# retroBreadboard_v1i1.net
KiCad netlist of a schematic drawn in Altium Designer
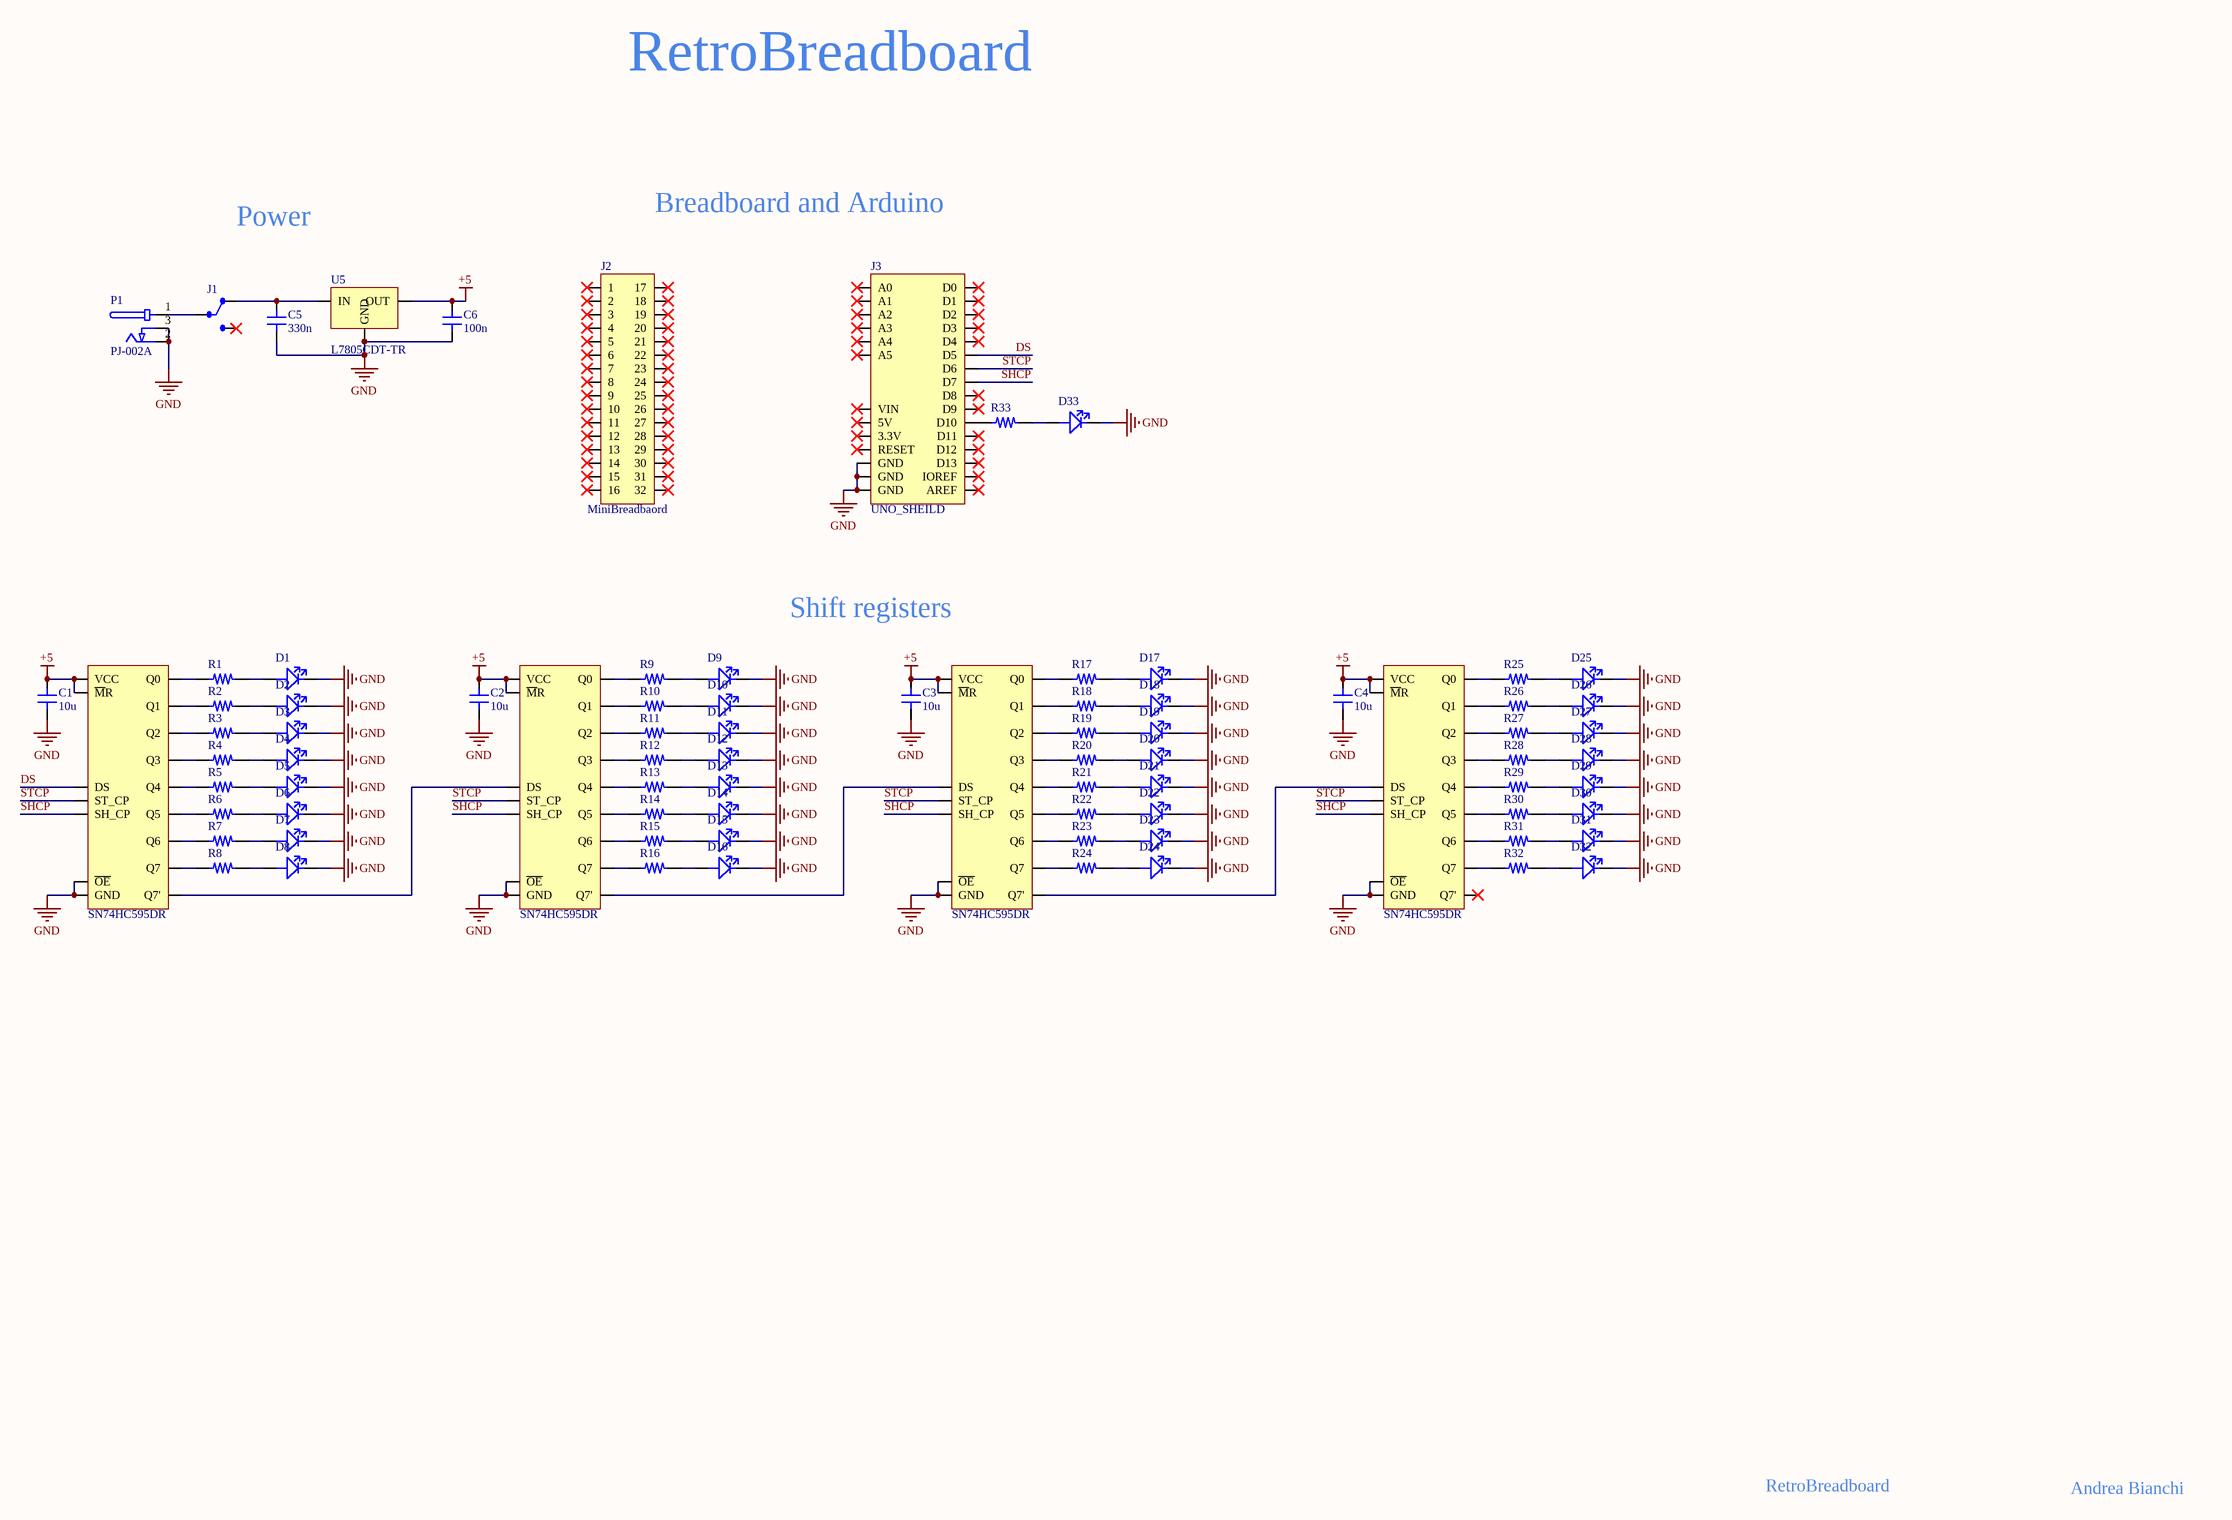
[diagram p0: retroBreadboard_v1i1.SchDoc]

(export (version "E")
  (design (tool "Eeschema 10.0.6"))
  (components
    (comp (ref "C1")
      (value "10u")
      (footprint "C0805")
      (fields
        (field (name "MANUFACTURER") "Samsung")
        (field (name "MANUFACTURER PART NUMBER") "CL21A106KQFNNNG")
        (field (name "TOLERANCE") "10%")
      )
      (libsource (lib "retroBreadboard_v1i1") (part "C0805_10u"))
    )
    (comp (ref "C2")
      (value "10u")
      (footprint "C0805")
      (fields
        (field (name "MANUFACTURER") "Samsung")
        (field (name "MANUFACTURER PART NUMBER") "CL21A106KQFNNNG")
        (field (name "TOLERANCE") "10%")
      )
      (libsource (lib "retroBreadboard_v1i1") (part "C0805_10u"))
    )
    (comp (ref "C3")
      (value "10u")
      (footprint "C0805")
      (fields
        (field (name "MANUFACTURER") "Samsung")
        (field (name "MANUFACTURER PART NUMBER") "CL21A106KQFNNNG")
        (field (name "TOLERANCE") "10%")
      )
      (libsource (lib "retroBreadboard_v1i1") (part "C0805_10u"))
    )
    (comp (ref "C4")
      (value "10u")
      (footprint "C0805")
      (fields
        (field (name "MANUFACTURER") "Samsung")
        (field (name "MANUFACTURER PART NUMBER") "CL21A106KQFNNNG")
        (field (name "TOLERANCE") "10%")
      )
      (libsource (lib "retroBreadboard_v1i1") (part "C0805_10u"))
    )
    (comp (ref "C5")
      (value "330n")
      (footprint "C0805")
      (fields
        (field (name "MANUFACTURER") "Samsung")
        (field (name "MANUFACTURER PART NUMBER") "CL21B334KAFNNNG")
        (field (name "TOLERANCE") "10%")
      )
      (libsource (lib "retroBreadboard_v1i1") (part "C0805_330n"))
    )
    (comp (ref "C6")
      (value "100n")
      (footprint "C0805")
      (fields
        (field (name "MANUFACTURER") "Samsung")
        (field (name "MANUFACTURER PART NUMBER") "CL21F104ZBCNNNC")
        (field (name "TOLERANCE") "80%")
      )
      (libsource (lib "retroBreadboard_v1i1") (part "C0805_100n"))
    )
    (comp (ref "D1")
      (value "VLMB1500-GS08")
      (footprint "VLMB1500-GS08")
      (description "Standard LEDs - SMD 0402 BLUE Non-Diff")
      (fields (field (name "MANUFACTURER") "Vishay"))
      (libsource (lib "retroBreadboard_v1i1") (part "VLMB1500-GS08"))
    )
    (comp (ref "D2")
      (value "VLMB1500-GS08")
      (footprint "VLMB1500-GS08")
      (description "Standard LEDs - SMD 0402 BLUE Non-Diff")
      (fields (field (name "MANUFACTURER") "Vishay"))
      (libsource (lib "retroBreadboard_v1i1") (part "VLMB1500-GS08"))
    )
    (comp (ref "D3")
      (value "VLMB1500-GS08")
      (footprint "VLMB1500-GS08")
      (description "Standard LEDs - SMD 0402 BLUE Non-Diff")
      (fields (field (name "MANUFACTURER") "Vishay"))
      (libsource (lib "retroBreadboard_v1i1") (part "VLMB1500-GS08"))
    )
    (comp (ref "D4")
      (value "VLMB1500-GS08")
      (footprint "VLMB1500-GS08")
      (description "Standard LEDs - SMD 0402 BLUE Non-Diff")
      (fields (field (name "MANUFACTURER") "Vishay"))
      (libsource (lib "retroBreadboard_v1i1") (part "VLMB1500-GS08"))
    )
    (comp (ref "D5")
      (value "VLMB1500-GS08")
      (footprint "VLMB1500-GS08")
      (description "Standard LEDs - SMD 0402 BLUE Non-Diff")
      (fields (field (name "MANUFACTURER") "Vishay"))
      (libsource (lib "retroBreadboard_v1i1") (part "VLMB1500-GS08"))
    )
    (comp (ref "D6")
      (value "VLMB1500-GS08")
      (footprint "VLMB1500-GS08")
      (description "Standard LEDs - SMD 0402 BLUE Non-Diff")
      (fields (field (name "MANUFACTURER") "Vishay"))
      (libsource (lib "retroBreadboard_v1i1") (part "VLMB1500-GS08"))
    )
    (comp (ref "D7")
      (value "VLMB1500-GS08")
      (footprint "VLMB1500-GS08")
      (description "Standard LEDs - SMD 0402 BLUE Non-Diff")
      (fields (field (name "MANUFACTURER") "Vishay"))
      (libsource (lib "retroBreadboard_v1i1") (part "VLMB1500-GS08"))
    )
    (comp (ref "D8")
      (value "VLMB1500-GS08")
      (footprint "VLMB1500-GS08")
      (description "Standard LEDs - SMD 0402 BLUE Non-Diff")
      (fields (field (name "MANUFACTURER") "Vishay"))
      (libsource (lib "retroBreadboard_v1i1") (part "VLMB1500-GS08"))
    )
    (comp (ref "D9")
      (value "VLMB1500-GS08")
      (footprint "VLMB1500-GS08")
      (description "Standard LEDs - SMD 0402 BLUE Non-Diff")
      (fields (field (name "MANUFACTURER") "Vishay"))
      (libsource (lib "retroBreadboard_v1i1") (part "VLMB1500-GS08"))
    )
    (comp (ref "D10")
      (value "VLMB1500-GS08")
      (footprint "VLMB1500-GS08")
      (description "Standard LEDs - SMD 0402 BLUE Non-Diff")
      (fields (field (name "MANUFACTURER") "Vishay"))
      (libsource (lib "retroBreadboard_v1i1") (part "VLMB1500-GS08"))
    )
    (comp (ref "D11")
      (value "VLMB1500-GS08")
      (footprint "VLMB1500-GS08")
      (description "Standard LEDs - SMD 0402 BLUE Non-Diff")
      (fields (field (name "MANUFACTURER") "Vishay"))
      (libsource (lib "retroBreadboard_v1i1") (part "VLMB1500-GS08"))
    )
    (comp (ref "D12")
      (value "VLMB1500-GS08")
      (footprint "VLMB1500-GS08")
      (description "Standard LEDs - SMD 0402 BLUE Non-Diff")
      (fields (field (name "MANUFACTURER") "Vishay"))
      (libsource (lib "retroBreadboard_v1i1") (part "VLMB1500-GS08"))
    )
    (comp (ref "D13")
      (value "VLMB1500-GS08")
      (footprint "VLMB1500-GS08")
      (description "Standard LEDs - SMD 0402 BLUE Non-Diff")
      (fields (field (name "MANUFACTURER") "Vishay"))
      (libsource (lib "retroBreadboard_v1i1") (part "VLMB1500-GS08"))
    )
    (comp (ref "D14")
      (value "VLMB1500-GS08")
      (footprint "VLMB1500-GS08")
      (description "Standard LEDs - SMD 0402 BLUE Non-Diff")
      (fields (field (name "MANUFACTURER") "Vishay"))
      (libsource (lib "retroBreadboard_v1i1") (part "VLMB1500-GS08"))
    )
    (comp (ref "D15")
      (value "VLMB1500-GS08")
      (footprint "VLMB1500-GS08")
      (description "Standard LEDs - SMD 0402 BLUE Non-Diff")
      (fields (field (name "MANUFACTURER") "Vishay"))
      (libsource (lib "retroBreadboard_v1i1") (part "VLMB1500-GS08"))
    )
    (comp (ref "D16")
      (value "VLMB1500-GS08")
      (footprint "VLMB1500-GS08")
      (description "Standard LEDs - SMD 0402 BLUE Non-Diff")
      (fields (field (name "MANUFACTURER") "Vishay"))
      (libsource (lib "retroBreadboard_v1i1") (part "VLMB1500-GS08"))
    )
    (comp (ref "D17")
      (value "VLMB1500-GS08")
      (footprint "VLMB1500-GS08")
      (description "Standard LEDs - SMD 0402 BLUE Non-Diff")
      (fields (field (name "MANUFACTURER") "Vishay"))
      (libsource (lib "retroBreadboard_v1i1") (part "VLMB1500-GS08"))
    )
    (comp (ref "D18")
      (value "VLMB1500-GS08")
      (footprint "VLMB1500-GS08")
      (description "Standard LEDs - SMD 0402 BLUE Non-Diff")
      (fields (field (name "MANUFACTURER") "Vishay"))
      (libsource (lib "retroBreadboard_v1i1") (part "VLMB1500-GS08"))
    )
    (comp (ref "D19")
      (value "VLMB1500-GS08")
      (footprint "VLMB1500-GS08")
      (description "Standard LEDs - SMD 0402 BLUE Non-Diff")
      (fields (field (name "MANUFACTURER") "Vishay"))
      (libsource (lib "retroBreadboard_v1i1") (part "VLMB1500-GS08"))
    )
    (comp (ref "D20")
      (value "VLMB1500-GS08")
      (footprint "VLMB1500-GS08")
      (description "Standard LEDs - SMD 0402 BLUE Non-Diff")
      (fields (field (name "MANUFACTURER") "Vishay"))
      (libsource (lib "retroBreadboard_v1i1") (part "VLMB1500-GS08"))
    )
    (comp (ref "D21")
      (value "VLMB1500-GS08")
      (footprint "VLMB1500-GS08")
      (description "Standard LEDs - SMD 0402 BLUE Non-Diff")
      (fields (field (name "MANUFACTURER") "Vishay"))
      (libsource (lib "retroBreadboard_v1i1") (part "VLMB1500-GS08"))
    )
    (comp (ref "D22")
      (value "VLMB1500-GS08")
      (footprint "VLMB1500-GS08")
      (description "Standard LEDs - SMD 0402 BLUE Non-Diff")
      (fields (field (name "MANUFACTURER") "Vishay"))
      (libsource (lib "retroBreadboard_v1i1") (part "VLMB1500-GS08"))
    )
    (comp (ref "D23")
      (value "VLMB1500-GS08")
      (footprint "VLMB1500-GS08")
      (description "Standard LEDs - SMD 0402 BLUE Non-Diff")
      (fields (field (name "MANUFACTURER") "Vishay"))
      (libsource (lib "retroBreadboard_v1i1") (part "VLMB1500-GS08"))
    )
    (comp (ref "D24")
      (value "VLMB1500-GS08")
      (footprint "VLMB1500-GS08")
      (description "Standard LEDs - SMD 0402 BLUE Non-Diff")
      (fields (field (name "MANUFACTURER") "Vishay"))
      (libsource (lib "retroBreadboard_v1i1") (part "VLMB1500-GS08"))
    )
    (comp (ref "D25")
      (value "VLMB1500-GS08")
      (footprint "VLMB1500-GS08")
      (description "Standard LEDs - SMD 0402 BLUE Non-Diff")
      (fields (field (name "MANUFACTURER") "Vishay"))
      (libsource (lib "retroBreadboard_v1i1") (part "VLMB1500-GS08"))
    )
    (comp (ref "D26")
      (value "VLMB1500-GS08")
      (footprint "VLMB1500-GS08")
      (description "Standard LEDs - SMD 0402 BLUE Non-Diff")
      (fields (field (name "MANUFACTURER") "Vishay"))
      (libsource (lib "retroBreadboard_v1i1") (part "VLMB1500-GS08"))
    )
    (comp (ref "D27")
      (value "VLMB1500-GS08")
      (footprint "VLMB1500-GS08")
      (description "Standard LEDs - SMD 0402 BLUE Non-Diff")
      (fields (field (name "MANUFACTURER") "Vishay"))
      (libsource (lib "retroBreadboard_v1i1") (part "VLMB1500-GS08"))
    )
    (comp (ref "D28")
      (value "VLMB1500-GS08")
      (footprint "VLMB1500-GS08")
      (description "Standard LEDs - SMD 0402 BLUE Non-Diff")
      (fields (field (name "MANUFACTURER") "Vishay"))
      (libsource (lib "retroBreadboard_v1i1") (part "VLMB1500-GS08"))
    )
    (comp (ref "D29")
      (value "VLMB1500-GS08")
      (footprint "VLMB1500-GS08")
      (description "Standard LEDs - SMD 0402 BLUE Non-Diff")
      (fields (field (name "MANUFACTURER") "Vishay"))
      (libsource (lib "retroBreadboard_v1i1") (part "VLMB1500-GS08"))
    )
    (comp (ref "D30")
      (value "VLMB1500-GS08")
      (footprint "VLMB1500-GS08")
      (description "Standard LEDs - SMD 0402 BLUE Non-Diff")
      (fields (field (name "MANUFACTURER") "Vishay"))
      (libsource (lib "retroBreadboard_v1i1") (part "VLMB1500-GS08"))
    )
    (comp (ref "D31")
      (value "VLMB1500-GS08")
      (footprint "VLMB1500-GS08")
      (description "Standard LEDs - SMD 0402 BLUE Non-Diff")
      (fields (field (name "MANUFACTURER") "Vishay"))
      (libsource (lib "retroBreadboard_v1i1") (part "VLMB1500-GS08"))
    )
    (comp (ref "D32")
      (value "VLMB1500-GS08")
      (footprint "VLMB1500-GS08")
      (description "Standard LEDs - SMD 0402 BLUE Non-Diff")
      (fields (field (name "MANUFACTURER") "Vishay"))
      (libsource (lib "retroBreadboard_v1i1") (part "VLMB1500-GS08"))
    )
    (comp (ref "D33")
      (value "VLMB1500-GS08")
      (footprint "VLMB1500-GS08")
      (description "Standard LEDs - SMD 0402 BLUE Non-Diff")
      (fields (field (name "MANUFACTURER") "Vishay"))
      (libsource (lib "retroBreadboard_v1i1") (part "VLMB1500-GS08"))
    )
    (comp (ref "J1")
      (value "500SSP1S1M6QEA")
      (footprint "SLIDE SPDT")
      (description "SWITCH SLIDE SPDT 5A 120V")
      (fields (field (name "MANUFACTURER") "E-Switch"))
      (libsource (lib "retroBreadboard_v1i1") (part "SLIDE SPDT"))
    )
    (comp (ref "J2")
      (value "MiniBreadbaord")
      (footprint "MINI_BREADBOARD HOLE")
      (description "Mini Breadboard")
      (fields
        (field (name "MANUFACTURER") "TE Connectivity AMP")
        (field (name "MANUFACTURER PART NUMBER") "1738132-1")
      )
      (libsource (lib "retroBreadboard_v1i1") (part "MINI_BREADBOARD"))
    )
    (comp (ref "J3")
      (value "UNO_SHEILD")
      (footprint "ARDUINO_UNO_SHIELD")
      (libsource (lib "retroBreadboard_v1i1") (part "ARDUINO_UNO_SHIELD"))
    )
    (comp (ref "P1")
      (value "PJ-002A")
      (footprint "PJ-002A")
      (description "PJ-002 Series 2 x 6.5 mm 16 V Right Angle Through Hole Power Jack")
      (fields (field (name "MANUFACTURER") "CUI"))
      (libsource (lib "retroBreadboard_v1i1") (part "PJ-002A"))
    )
    (comp (ref "R1")
      (value "RC0402FR-07200RL")
      (footprint "RES0402")
      (description "RES SMD 200 OHM 1% 1/16W 0402")
      (fields (field (name "MANUFACTURER") "Yageo") (field (name "TOLERANCE") "1%"))
      (libsource (lib "retroBreadboard_v1i1") (part "R0402_200"))
    )
    (comp (ref "R2")
      (value "RC0402FR-07200RL")
      (footprint "RES0402")
      (description "RES SMD 200 OHM 1% 1/16W 0402")
      (fields (field (name "MANUFACTURER") "Yageo") (field (name "TOLERANCE") "1%"))
      (libsource (lib "retroBreadboard_v1i1") (part "R0402_200"))
    )
    (comp (ref "R3")
      (value "RC0402FR-07200RL")
      (footprint "RES0402")
      (description "RES SMD 200 OHM 1% 1/16W 0402")
      (fields (field (name "MANUFACTURER") "Yageo") (field (name "TOLERANCE") "1%"))
      (libsource (lib "retroBreadboard_v1i1") (part "R0402_200"))
    )
    (comp (ref "R4")
      (value "RC0402FR-07200RL")
      (footprint "RES0402")
      (description "RES SMD 200 OHM 1% 1/16W 0402")
      (fields (field (name "MANUFACTURER") "Yageo") (field (name "TOLERANCE") "1%"))
      (libsource (lib "retroBreadboard_v1i1") (part "R0402_200"))
    )
    (comp (ref "R5")
      (value "RC0402FR-07200RL")
      (footprint "RES0402")
      (description "RES SMD 200 OHM 1% 1/16W 0402")
      (fields (field (name "MANUFACTURER") "Yageo") (field (name "TOLERANCE") "1%"))
      (libsource (lib "retroBreadboard_v1i1") (part "R0402_200"))
    )
    (comp (ref "R6")
      (value "RC0402FR-07200RL")
      (footprint "RES0402")
      (description "RES SMD 200 OHM 1% 1/16W 0402")
      (fields (field (name "MANUFACTURER") "Yageo") (field (name "TOLERANCE") "1%"))
      (libsource (lib "retroBreadboard_v1i1") (part "R0402_200"))
    )
    (comp (ref "R7")
      (value "RC0402FR-07200RL")
      (footprint "RES0402")
      (description "RES SMD 200 OHM 1% 1/16W 0402")
      (fields (field (name "MANUFACTURER") "Yageo") (field (name "TOLERANCE") "1%"))
      (libsource (lib "retroBreadboard_v1i1") (part "R0402_200"))
    )
    (comp (ref "R8")
      (value "RC0402FR-07200RL")
      (footprint "RES0402")
      (description "RES SMD 200 OHM 1% 1/16W 0402")
      (fields (field (name "MANUFACTURER") "Yageo") (field (name "TOLERANCE") "1%"))
      (libsource (lib "retroBreadboard_v1i1") (part "R0402_200"))
    )
    (comp (ref "R9")
      (value "RC0402FR-07200RL")
      (footprint "RES0402")
      (description "RES SMD 200 OHM 1% 1/16W 0402")
      (fields (field (name "MANUFACTURER") "Yageo") (field (name "TOLERANCE") "1%"))
      (libsource (lib "retroBreadboard_v1i1") (part "R0402_200"))
    )
    (comp (ref "R10")
      (value "RC0402FR-07200RL")
      (footprint "RES0402")
      (description "RES SMD 200 OHM 1% 1/16W 0402")
      (fields (field (name "MANUFACTURER") "Yageo") (field (name "TOLERANCE") "1%"))
      (libsource (lib "retroBreadboard_v1i1") (part "R0402_200"))
    )
    (comp (ref "R11")
      (value "RC0402FR-07200RL")
      (footprint "RES0402")
      (description "RES SMD 200 OHM 1% 1/16W 0402")
      (fields (field (name "MANUFACTURER") "Yageo") (field (name "TOLERANCE") "1%"))
      (libsource (lib "retroBreadboard_v1i1") (part "R0402_200"))
    )
    (comp (ref "R12")
      (value "RC0402FR-07200RL")
      (footprint "RES0402")
      (description "RES SMD 200 OHM 1% 1/16W 0402")
      (fields (field (name "MANUFACTURER") "Yageo") (field (name "TOLERANCE") "1%"))
      (libsource (lib "retroBreadboard_v1i1") (part "R0402_200"))
    )
    (comp (ref "R13")
      (value "RC0402FR-07200RL")
      (footprint "RES0402")
      (description "RES SMD 200 OHM 1% 1/16W 0402")
      (fields (field (name "MANUFACTURER") "Yageo") (field (name "TOLERANCE") "1%"))
      (libsource (lib "retroBreadboard_v1i1") (part "R0402_200"))
    )
    (comp (ref "R14")
      (value "RC0402FR-07200RL")
      (footprint "RES0402")
      (description "RES SMD 200 OHM 1% 1/16W 0402")
      (fields (field (name "MANUFACTURER") "Yageo") (field (name "TOLERANCE") "1%"))
      (libsource (lib "retroBreadboard_v1i1") (part "R0402_200"))
    )
    (comp (ref "R15")
      (value "RC0402FR-07200RL")
      (footprint "RES0402")
      (description "RES SMD 200 OHM 1% 1/16W 0402")
      (fields (field (name "MANUFACTURER") "Yageo") (field (name "TOLERANCE") "1%"))
      (libsource (lib "retroBreadboard_v1i1") (part "R0402_200"))
    )
    (comp (ref "R16")
      (value "RC0402FR-07200RL")
      (footprint "RES0402")
      (description "RES SMD 200 OHM 1% 1/16W 0402")
      (fields (field (name "MANUFACTURER") "Yageo") (field (name "TOLERANCE") "1%"))
      (libsource (lib "retroBreadboard_v1i1") (part "R0402_200"))
    )
    (comp (ref "R17")
      (value "RC0402FR-07200RL")
      (footprint "RES0402")
      (description "RES SMD 200 OHM 1% 1/16W 0402")
      (fields (field (name "MANUFACTURER") "Yageo") (field (name "TOLERANCE") "1%"))
      (libsource (lib "retroBreadboard_v1i1") (part "R0402_200"))
    )
    (comp (ref "R18")
      (value "RC0402FR-07200RL")
      (footprint "RES0402")
      (description "RES SMD 200 OHM 1% 1/16W 0402")
      (fields (field (name "MANUFACTURER") "Yageo") (field (name "TOLERANCE") "1%"))
      (libsource (lib "retroBreadboard_v1i1") (part "R0402_200"))
    )
    (comp (ref "R19")
      (value "RC0402FR-07200RL")
      (footprint "RES0402")
      (description "RES SMD 200 OHM 1% 1/16W 0402")
      (fields (field (name "MANUFACTURER") "Yageo") (field (name "TOLERANCE") "1%"))
      (libsource (lib "retroBreadboard_v1i1") (part "R0402_200"))
    )
    (comp (ref "R20")
      (value "RC0402FR-07200RL")
      (footprint "RES0402")
      (description "RES SMD 200 OHM 1% 1/16W 0402")
      (fields (field (name "MANUFACTURER") "Yageo") (field (name "TOLERANCE") "1%"))
      (libsource (lib "retroBreadboard_v1i1") (part "R0402_200"))
    )
    (comp (ref "R21")
      (value "RC0402FR-07200RL")
      (footprint "RES0402")
      (description "RES SMD 200 OHM 1% 1/16W 0402")
      (fields (field (name "MANUFACTURER") "Yageo") (field (name "TOLERANCE") "1%"))
      (libsource (lib "retroBreadboard_v1i1") (part "R0402_200"))
    )
    (comp (ref "R22")
      (value "RC0402FR-07200RL")
      (footprint "RES0402")
      (description "RES SMD 200 OHM 1% 1/16W 0402")
      (fields (field (name "MANUFACTURER") "Yageo") (field (name "TOLERANCE") "1%"))
      (libsource (lib "retroBreadboard_v1i1") (part "R0402_200"))
    )
    (comp (ref "R23")
      (value "RC0402FR-07200RL")
      (footprint "RES0402")
      (description "RES SMD 200 OHM 1% 1/16W 0402")
      (fields (field (name "MANUFACTURER") "Yageo") (field (name "TOLERANCE") "1%"))
      (libsource (lib "retroBreadboard_v1i1") (part "R0402_200"))
    )
    (comp (ref "R24")
      (value "RC0402FR-07200RL")
      (footprint "RES0402")
      (description "RES SMD 200 OHM 1% 1/16W 0402")
      (fields (field (name "MANUFACTURER") "Yageo") (field (name "TOLERANCE") "1%"))
      (libsource (lib "retroBreadboard_v1i1") (part "R0402_200"))
    )
    (comp (ref "R25")
      (value "RC0402FR-07200RL")
      (footprint "RES0402")
      (description "RES SMD 200 OHM 1% 1/16W 0402")
      (fields (field (name "MANUFACTURER") "Yageo") (field (name "TOLERANCE") "1%"))
      (libsource (lib "retroBreadboard_v1i1") (part "R0402_200"))
    )
    (comp (ref "R26")
      (value "RC0402FR-07200RL")
      (footprint "RES0402")
      (description "RES SMD 200 OHM 1% 1/16W 0402")
      (fields (field (name "MANUFACTURER") "Yageo") (field (name "TOLERANCE") "1%"))
      (libsource (lib "retroBreadboard_v1i1") (part "R0402_200"))
    )
    (comp (ref "R27")
      (value "RC0402FR-07200RL")
      (footprint "RES0402")
      (description "RES SMD 200 OHM 1% 1/16W 0402")
      (fields (field (name "MANUFACTURER") "Yageo") (field (name "TOLERANCE") "1%"))
      (libsource (lib "retroBreadboard_v1i1") (part "R0402_200"))
    )
    (comp (ref "R28")
      (value "RC0402FR-07200RL")
      (footprint "RES0402")
      (description "RES SMD 200 OHM 1% 1/16W 0402")
      (fields (field (name "MANUFACTURER") "Yageo") (field (name "TOLERANCE") "1%"))
      (libsource (lib "retroBreadboard_v1i1") (part "R0402_200"))
    )
    (comp (ref "R29")
      (value "RC0402FR-07200RL")
      (footprint "RES0402")
      (description "RES SMD 200 OHM 1% 1/16W 0402")
      (fields (field (name "MANUFACTURER") "Yageo") (field (name "TOLERANCE") "1%"))
      (libsource (lib "retroBreadboard_v1i1") (part "R0402_200"))
    )
    (comp (ref "R30")
      (value "RC0402FR-07200RL")
      (footprint "RES0402")
      (description "RES SMD 200 OHM 1% 1/16W 0402")
      (fields (field (name "MANUFACTURER") "Yageo") (field (name "TOLERANCE") "1%"))
      (libsource (lib "retroBreadboard_v1i1") (part "R0402_200"))
    )
    (comp (ref "R31")
      (value "RC0402FR-07200RL")
      (footprint "RES0402")
      (description "RES SMD 200 OHM 1% 1/16W 0402")
      (fields (field (name "MANUFACTURER") "Yageo") (field (name "TOLERANCE") "1%"))
      (libsource (lib "retroBreadboard_v1i1") (part "R0402_200"))
    )
    (comp (ref "R32")
      (value "RC0402FR-07200RL")
      (footprint "RES0402")
      (description "RES SMD 200 OHM 1% 1/16W 0402")
      (fields (field (name "MANUFACTURER") "Yageo") (field (name "TOLERANCE") "1%"))
      (libsource (lib "retroBreadboard_v1i1") (part "R0402_200"))
    )
    (comp (ref "R33")
      (value "RC0402FR-07200RL")
      (footprint "RES0402")
      (description "RES SMD 200 OHM 1% 1/16W 0402")
      (fields (field (name "MANUFACTURER") "Yageo") (field (name "TOLERANCE") "1%"))
      (libsource (lib "retroBreadboard_v1i1") (part "R0402_200"))
    )
    (comp (ref "U1")
      (value "SN74HC595DR")
      (footprint "SOIC16")
      (description "IC, SM, LOGIC, 74HC, REGISTER")
      (fields (field (name "MANUFACTURER") "Texas Instruments"))
      (libsource (lib "retroBreadboard_v1i1") (part "74HC595"))
    )
    (comp (ref "U2")
      (value "SN74HC595DR")
      (footprint "SOIC16")
      (description "IC, SM, LOGIC, 74HC, REGISTER")
      (fields (field (name "MANUFACTURER") "Texas Instruments"))
      (libsource (lib "retroBreadboard_v1i1") (part "74HC595"))
    )
    (comp (ref "U3")
      (value "SN74HC595DR")
      (footprint "SOIC16")
      (description "IC, SM, LOGIC, 74HC, REGISTER")
      (fields (field (name "MANUFACTURER") "Texas Instruments"))
      (libsource (lib "retroBreadboard_v1i1") (part "74HC595"))
    )
    (comp (ref "U4")
      (value "SN74HC595DR")
      (footprint "SOIC16")
      (description "IC, SM, LOGIC, 74HC, REGISTER")
      (fields (field (name "MANUFACTURER") "Texas Instruments"))
      (libsource (lib "retroBreadboard_v1i1") (part "74HC595"))
    )
    (comp (ref "U5")
      (value "L7805CDT-TR")
      (footprint "DPAK")
      (description "IC REG LDO 5V 1.5A DPAK")
      (fields (field (name "MANUFACTURER") "STMicroelectronics"))
      (libsource (lib "retroBreadboard_v1i1") (part "L7805CDT-TR"))
    )
  )
  (nets
    (net (code "1") (name "+5") (class "Default")
      (node (ref "C1") (pin "2") (pinfunction "2_2") (pintype "passive"))
      (node (ref "C2") (pin "2") (pinfunction "2_2") (pintype "passive"))
      (node (ref "C3") (pin "2") (pinfunction "2_2") (pintype "passive"))
      (node (ref "C4") (pin "2") (pinfunction "2_2") (pintype "passive"))
      (node (ref "C6") (pin "2") (pinfunction "2_2") (pintype "passive"))
      (node (ref "U1") (pin "10") (pinfunction "~{M}R_10") (pintype "passive"))
      (node (ref "U1") (pin "16") (pinfunction "VCC_16") (pintype "passive"))
      (node (ref "U2") (pin "10") (pinfunction "~{M}R_10") (pintype "passive"))
      (node (ref "U2") (pin "16") (pinfunction "VCC_16") (pintype "passive"))
      (node (ref "U3") (pin "10") (pinfunction "~{M}R_10") (pintype "passive"))
      (node (ref "U3") (pin "16") (pinfunction "VCC_16") (pintype "passive"))
      (node (ref "U4") (pin "10") (pinfunction "~{M}R_10") (pintype "passive"))
      (node (ref "U4") (pin "16") (pinfunction "VCC_16") (pintype "passive"))
      (node (ref "U5") (pin "3") (pinfunction "OUT_3") (pintype "passive"))
    )
    (net (code "2") (name "/DS") (class "Default")
      (node (ref "J3") (pin "6") (pinfunction "D5_6") (pintype "passive"))
      (node (ref "U1") (pin "14") (pinfunction "DS_14") (pintype "passive"))
    )
    (net (code "3") (name "/SHCP") (class "Default")
      (node (ref "J3") (pin "8") (pinfunction "D7_8") (pintype "passive"))
      (node (ref "U1") (pin "11") (pinfunction "SH_CP_11") (pintype "passive"))
      (node (ref "U2") (pin "11") (pinfunction "SH_CP_11") (pintype "passive"))
      (node (ref "U3") (pin "11") (pinfunction "SH_CP_11") (pintype "passive"))
      (node (ref "U4") (pin "11") (pinfunction "SH_CP_11") (pintype "passive"))
    )
    (net (code "4") (name "/STCP") (class "Default")
      (node (ref "J3") (pin "7") (pinfunction "D6_7") (pintype "passive"))
      (node (ref "U1") (pin "12") (pinfunction "ST_CP_12") (pintype "passive"))
      (node (ref "U2") (pin "12") (pinfunction "ST_CP_12") (pintype "passive"))
      (node (ref "U3") (pin "12") (pinfunction "ST_CP_12") (pintype "passive"))
      (node (ref "U4") (pin "12") (pinfunction "ST_CP_12") (pintype "passive"))
    )
    (net (code "5") (name "GND") (class "Default")
      (node (ref "C1") (pin "1") (pinfunction "1_1") (pintype "passive"))
      (node (ref "C2") (pin "1") (pinfunction "1_1") (pintype "passive"))
      (node (ref "C3") (pin "1") (pinfunction "1_1") (pintype "passive"))
      (node (ref "C4") (pin "1") (pinfunction "1_1") (pintype "passive"))
      (node (ref "C5") (pin "1") (pinfunction "1_1") (pintype "passive"))
      (node (ref "C6") (pin "1") (pinfunction "1_1") (pintype "passive"))
      (node (ref "D1") (pin "2") (pinfunction "K_2") (pintype "passive"))
      (node (ref "D10") (pin "2") (pinfunction "K_2") (pintype "passive"))
      (node (ref "D11") (pin "2") (pinfunction "K_2") (pintype "passive"))
      (node (ref "D12") (pin "2") (pinfunction "K_2") (pintype "passive"))
      (node (ref "D13") (pin "2") (pinfunction "K_2") (pintype "passive"))
      (node (ref "D14") (pin "2") (pinfunction "K_2") (pintype "passive"))
      (node (ref "D15") (pin "2") (pinfunction "K_2") (pintype "passive"))
      (node (ref "D16") (pin "2") (pinfunction "K_2") (pintype "passive"))
      (node (ref "D17") (pin "2") (pinfunction "K_2") (pintype "passive"))
      (node (ref "D18") (pin "2") (pinfunction "K_2") (pintype "passive"))
      (node (ref "D19") (pin "2") (pinfunction "K_2") (pintype "passive"))
      (node (ref "D2") (pin "2") (pinfunction "K_2") (pintype "passive"))
      (node (ref "D20") (pin "2") (pinfunction "K_2") (pintype "passive"))
      (node (ref "D21") (pin "2") (pinfunction "K_2") (pintype "passive"))
      (node (ref "D22") (pin "2") (pinfunction "K_2") (pintype "passive"))
      (node (ref "D23") (pin "2") (pinfunction "K_2") (pintype "passive"))
      (node (ref "D24") (pin "2") (pinfunction "K_2") (pintype "passive"))
      (node (ref "D25") (pin "2") (pinfunction "K_2") (pintype "passive"))
      (node (ref "D26") (pin "2") (pinfunction "K_2") (pintype "passive"))
      (node (ref "D27") (pin "2") (pinfunction "K_2") (pintype "passive"))
      (node (ref "D28") (pin "2") (pinfunction "K_2") (pintype "passive"))
      (node (ref "D29") (pin "2") (pinfunction "K_2") (pintype "passive"))
      (node (ref "D3") (pin "2") (pinfunction "K_2") (pintype "passive"))
      (node (ref "D30") (pin "2") (pinfunction "K_2") (pintype "passive"))
      (node (ref "D31") (pin "2") (pinfunction "K_2") (pintype "passive"))
      (node (ref "D32") (pin "2") (pinfunction "K_2") (pintype "passive"))
      (node (ref "D33") (pin "2") (pinfunction "K_2") (pintype "passive"))
      (node (ref "D4") (pin "2") (pinfunction "K_2") (pintype "passive"))
      (node (ref "D5") (pin "2") (pinfunction "K_2") (pintype "passive"))
      (node (ref "D6") (pin "2") (pinfunction "K_2") (pintype "passive"))
      (node (ref "D7") (pin "2") (pinfunction "K_2") (pintype "passive"))
      (node (ref "D8") (pin "2") (pinfunction "K_2") (pintype "passive"))
      (node (ref "D9") (pin "2") (pinfunction "K_2") (pintype "passive"))
      (node (ref "J3") (pin "15") (pinfunction "GND_15") (pintype "passive"))
      (node (ref "J3") (pin "24") (pinfunction "GND_24") (pintype "passive"))
      (node (ref "J3") (pin "25") (pinfunction "GND_25") (pintype "passive"))
      (node (ref "P1") (pin "2") (pinfunction "3_2") (pintype "passive"))
      (node (ref "P1") (pin "3") (pinfunction "2_3") (pintype "passive"))
      (node (ref "U1") (pin "13") (pinfunction "~{OE}_13") (pintype "passive"))
      (node (ref "U1") (pin "8") (pinfunction "GND_8") (pintype "passive"))
      (node (ref "U2") (pin "13") (pinfunction "~{OE}_13") (pintype "passive"))
      (node (ref "U2") (pin "8") (pinfunction "GND_8") (pintype "passive"))
      (node (ref "U3") (pin "13") (pinfunction "~{OE}_13") (pintype "passive"))
      (node (ref "U3") (pin "8") (pinfunction "GND_8") (pintype "passive"))
      (node (ref "U4") (pin "13") (pinfunction "~{OE}_13") (pintype "passive"))
      (node (ref "U4") (pin "8") (pinfunction "GND_8") (pintype "passive"))
      (node (ref "U5") (pin "4") (pinfunction "GND_4") (pintype "passive"))
    )
    (net (code "6") (name "Net-(D1-A)") (class "Default")
      (node (ref "D1") (pin "1") (pinfunction "A_1") (pintype "passive"))
      (node (ref "R1") (pin "2") (pinfunction "2_2") (pintype "passive"))
    )
    (net (code "7") (name "Net-(D2-A)") (class "Default")
      (node (ref "D2") (pin "1") (pinfunction "A_1") (pintype "passive"))
      (node (ref "R2") (pin "2") (pinfunction "2_2") (pintype "passive"))
    )
    (net (code "8") (name "Net-(D3-A)") (class "Default")
      (node (ref "D3") (pin "1") (pinfunction "A_1") (pintype "passive"))
      (node (ref "R3") (pin "2") (pinfunction "2_2") (pintype "passive"))
    )
    (net (code "9") (name "Net-(D4-A)") (class "Default")
      (node (ref "D4") (pin "1") (pinfunction "A_1") (pintype "passive"))
      (node (ref "R4") (pin "2") (pinfunction "2_2") (pintype "passive"))
    )
    (net (code "10") (name "Net-(D5-A)") (class "Default")
      (node (ref "D5") (pin "1") (pinfunction "A_1") (pintype "passive"))
      (node (ref "R5") (pin "2") (pinfunction "2_2") (pintype "passive"))
    )
    (net (code "11") (name "Net-(D6-A)") (class "Default")
      (node (ref "D6") (pin "1") (pinfunction "A_1") (pintype "passive"))
      (node (ref "R6") (pin "2") (pinfunction "2_2") (pintype "passive"))
    )
    (net (code "12") (name "Net-(D7-A)") (class "Default")
      (node (ref "D7") (pin "1") (pinfunction "A_1") (pintype "passive"))
      (node (ref "R7") (pin "2") (pinfunction "2_2") (pintype "passive"))
    )
    (net (code "13") (name "Net-(D8-A)") (class "Default")
      (node (ref "D8") (pin "1") (pinfunction "A_1") (pintype "passive"))
      (node (ref "R8") (pin "2") (pinfunction "2_2") (pintype "passive"))
    )
    (net (code "14") (name "Net-(D9-A)") (class "Default")
      (node (ref "D9") (pin "1") (pinfunction "A_1") (pintype "passive"))
      (node (ref "R9") (pin "2") (pinfunction "2_2") (pintype "passive"))
    )
    (net (code "15") (name "Net-(D10-A)") (class "Default")
      (node (ref "D10") (pin "1") (pinfunction "A_1") (pintype "passive"))
      (node (ref "R10") (pin "2") (pinfunction "2_2") (pintype "passive"))
    )
    (net (code "16") (name "Net-(D11-A)") (class "Default")
      (node (ref "D11") (pin "1") (pinfunction "A_1") (pintype "passive"))
      (node (ref "R11") (pin "2") (pinfunction "2_2") (pintype "passive"))
    )
    (net (code "17") (name "Net-(D12-A)") (class "Default")
      (node (ref "D12") (pin "1") (pinfunction "A_1") (pintype "passive"))
      (node (ref "R12") (pin "2") (pinfunction "2_2") (pintype "passive"))
    )
    (net (code "18") (name "Net-(D13-A)") (class "Default")
      (node (ref "D13") (pin "1") (pinfunction "A_1") (pintype "passive"))
      (node (ref "R13") (pin "2") (pinfunction "2_2") (pintype "passive"))
    )
    (net (code "19") (name "Net-(D14-A)") (class "Default")
      (node (ref "D14") (pin "1") (pinfunction "A_1") (pintype "passive"))
      (node (ref "R14") (pin "2") (pinfunction "2_2") (pintype "passive"))
    )
    (net (code "20") (name "Net-(D15-A)") (class "Default")
      (node (ref "D15") (pin "1") (pinfunction "A_1") (pintype "passive"))
      (node (ref "R15") (pin "2") (pinfunction "2_2") (pintype "passive"))
    )
    (net (code "21") (name "Net-(D16-A)") (class "Default")
      (node (ref "D16") (pin "1") (pinfunction "A_1") (pintype "passive"))
      (node (ref "R16") (pin "2") (pinfunction "2_2") (pintype "passive"))
    )
    (net (code "22") (name "Net-(D17-A)") (class "Default")
      (node (ref "D17") (pin "1") (pinfunction "A_1") (pintype "passive"))
      (node (ref "R17") (pin "2") (pinfunction "2_2") (pintype "passive"))
    )
    (net (code "23") (name "Net-(D18-A)") (class "Default")
      (node (ref "D18") (pin "1") (pinfunction "A_1") (pintype "passive"))
      (node (ref "R18") (pin "2") (pinfunction "2_2") (pintype "passive"))
    )
    (net (code "24") (name "Net-(D19-A)") (class "Default")
      (node (ref "D19") (pin "1") (pinfunction "A_1") (pintype "passive"))
      (node (ref "R19") (pin "2") (pinfunction "2_2") (pintype "passive"))
    )
    (net (code "25") (name "Net-(D20-A)") (class "Default")
      (node (ref "D20") (pin "1") (pinfunction "A_1") (pintype "passive"))
      (node (ref "R20") (pin "2") (pinfunction "2_2") (pintype "passive"))
    )
    (net (code "26") (name "Net-(D21-A)") (class "Default")
      (node (ref "D21") (pin "1") (pinfunction "A_1") (pintype "passive"))
      (node (ref "R21") (pin "2") (pinfunction "2_2") (pintype "passive"))
    )
    (net (code "27") (name "Net-(D22-A)") (class "Default")
      (node (ref "D22") (pin "1") (pinfunction "A_1") (pintype "passive"))
      (node (ref "R22") (pin "2") (pinfunction "2_2") (pintype "passive"))
    )
    (net (code "28") (name "Net-(D23-A)") (class "Default")
      (node (ref "D23") (pin "1") (pinfunction "A_1") (pintype "passive"))
      (node (ref "R23") (pin "2") (pinfunction "2_2") (pintype "passive"))
    )
    (net (code "29") (name "Net-(D24-A)") (class "Default")
      (node (ref "D24") (pin "1") (pinfunction "A_1") (pintype "passive"))
      (node (ref "R24") (pin "2") (pinfunction "2_2") (pintype "passive"))
    )
    (net (code "30") (name "Net-(D25-A)") (class "Default")
      (node (ref "D25") (pin "1") (pinfunction "A_1") (pintype "passive"))
      (node (ref "R25") (pin "2") (pinfunction "2_2") (pintype "passive"))
    )
    (net (code "31") (name "Net-(D26-A)") (class "Default")
      (node (ref "D26") (pin "1") (pinfunction "A_1") (pintype "passive"))
      (node (ref "R26") (pin "2") (pinfunction "2_2") (pintype "passive"))
    )
    (net (code "32") (name "Net-(D27-A)") (class "Default")
      (node (ref "D27") (pin "1") (pinfunction "A_1") (pintype "passive"))
      (node (ref "R27") (pin "2") (pinfunction "2_2") (pintype "passive"))
    )
    (net (code "33") (name "Net-(D28-A)") (class "Default")
      (node (ref "D28") (pin "1") (pinfunction "A_1") (pintype "passive"))
      (node (ref "R28") (pin "2") (pinfunction "2_2") (pintype "passive"))
    )
    (net (code "34") (name "Net-(D29-A)") (class "Default")
      (node (ref "D29") (pin "1") (pinfunction "A_1") (pintype "passive"))
      (node (ref "R29") (pin "2") (pinfunction "2_2") (pintype "passive"))
    )
    (net (code "35") (name "Net-(D30-A)") (class "Default")
      (node (ref "D30") (pin "1") (pinfunction "A_1") (pintype "passive"))
      (node (ref "R30") (pin "2") (pinfunction "2_2") (pintype "passive"))
    )
    (net (code "36") (name "Net-(D31-A)") (class "Default")
      (node (ref "D31") (pin "1") (pinfunction "A_1") (pintype "passive"))
      (node (ref "R31") (pin "2") (pinfunction "2_2") (pintype "passive"))
    )
    (net (code "37") (name "Net-(D32-A)") (class "Default")
      (node (ref "D32") (pin "1") (pinfunction "A_1") (pintype "passive"))
      (node (ref "R32") (pin "2") (pinfunction "2_2") (pintype "passive"))
    )
    (net (code "38") (name "Net-(D33-A)") (class "Default")
      (node (ref "D33") (pin "1") (pinfunction "A_1") (pintype "passive"))
      (node (ref "R33") (pin "2") (pinfunction "2_2") (pintype "passive"))
    )
    (net (code "39") (name "Net-(J1-Pad2)") (class "Default")
      (node (ref "J1") (pin "2") (pinfunction "2_2") (pintype "passive"))
      (node (ref "P1") (pin "1") (pinfunction "1_1") (pintype "passive"))
    )
    (net (code "40") (name "Net-(J3-D10)") (class "Default")
      (node (ref "J3") (pin "11") (pinfunction "D10_11") (pintype "passive"))
      (node (ref "R33") (pin "1") (pinfunction "1_1") (pintype "passive"))
    )
    (net (code "41") (name "Net-(U1-Q0)") (class "Default")
      (node (ref "R1") (pin "1") (pinfunction "1_1") (pintype "passive"))
      (node (ref "U1") (pin "15") (pinfunction "Q0_15") (pintype "passive"))
    )
    (net (code "42") (name "Net-(U1-Q1)") (class "Default")
      (node (ref "R2") (pin "1") (pinfunction "1_1") (pintype "passive"))
      (node (ref "U1") (pin "1") (pinfunction "Q1_1") (pintype "passive"))
    )
    (net (code "43") (name "Net-(U1-Q2)") (class "Default")
      (node (ref "R3") (pin "1") (pinfunction "1_1") (pintype "passive"))
      (node (ref "U1") (pin "2") (pinfunction "Q2_2") (pintype "passive"))
    )
    (net (code "44") (name "Net-(U1-Q3)") (class "Default")
      (node (ref "R4") (pin "1") (pinfunction "1_1") (pintype "passive"))
      (node (ref "U1") (pin "3") (pinfunction "Q3_3") (pintype "passive"))
    )
    (net (code "45") (name "Net-(U1-Q4)") (class "Default")
      (node (ref "R5") (pin "1") (pinfunction "1_1") (pintype "passive"))
      (node (ref "U1") (pin "4") (pinfunction "Q4_4") (pintype "passive"))
    )
    (net (code "46") (name "Net-(U1-Q5)") (class "Default")
      (node (ref "R6") (pin "1") (pinfunction "1_1") (pintype "passive"))
      (node (ref "U1") (pin "5") (pinfunction "Q5_5") (pintype "passive"))
    )
    (net (code "47") (name "Net-(U1-Q6)") (class "Default")
      (node (ref "R7") (pin "1") (pinfunction "1_1") (pintype "passive"))
      (node (ref "U1") (pin "6") (pinfunction "Q6_6") (pintype "passive"))
    )
    (net (code "48") (name "Net-(U1-Q7')") (class "Default")
      (node (ref "U1") (pin "9") (pinfunction "Q7'_9") (pintype "passive"))
      (node (ref "U2") (pin "14") (pinfunction "DS_14") (pintype "passive"))
    )
    (net (code "49") (name "Net-(U1-Q7)") (class "Default")
      (node (ref "R8") (pin "1") (pinfunction "1_1") (pintype "passive"))
      (node (ref "U1") (pin "7") (pinfunction "Q7_7") (pintype "passive"))
    )
    (net (code "50") (name "Net-(U2-Q0)") (class "Default")
      (node (ref "R9") (pin "1") (pinfunction "1_1") (pintype "passive"))
      (node (ref "U2") (pin "15") (pinfunction "Q0_15") (pintype "passive"))
    )
    (net (code "51") (name "Net-(U2-Q1)") (class "Default")
      (node (ref "R10") (pin "1") (pinfunction "1_1") (pintype "passive"))
      (node (ref "U2") (pin "1") (pinfunction "Q1_1") (pintype "passive"))
    )
    (net (code "52") (name "Net-(U2-Q2)") (class "Default")
      (node (ref "R11") (pin "1") (pinfunction "1_1") (pintype "passive"))
      (node (ref "U2") (pin "2") (pinfunction "Q2_2") (pintype "passive"))
    )
    (net (code "53") (name "Net-(U2-Q3)") (class "Default")
      (node (ref "R12") (pin "1") (pinfunction "1_1") (pintype "passive"))
      (node (ref "U2") (pin "3") (pinfunction "Q3_3") (pintype "passive"))
    )
    (net (code "54") (name "Net-(U2-Q4)") (class "Default")
      (node (ref "R13") (pin "1") (pinfunction "1_1") (pintype "passive"))
      (node (ref "U2") (pin "4") (pinfunction "Q4_4") (pintype "passive"))
    )
    (net (code "55") (name "Net-(U2-Q5)") (class "Default")
      (node (ref "R14") (pin "1") (pinfunction "1_1") (pintype "passive"))
      (node (ref "U2") (pin "5") (pinfunction "Q5_5") (pintype "passive"))
    )
    (net (code "56") (name "Net-(U2-Q6)") (class "Default")
      (node (ref "R15") (pin "1") (pinfunction "1_1") (pintype "passive"))
      (node (ref "U2") (pin "6") (pinfunction "Q6_6") (pintype "passive"))
    )
    (net (code "57") (name "Net-(U2-Q7')") (class "Default")
      (node (ref "U2") (pin "9") (pinfunction "Q7'_9") (pintype "passive"))
      (node (ref "U3") (pin "14") (pinfunction "DS_14") (pintype "passive"))
    )
    (net (code "58") (name "Net-(U2-Q7)") (class "Default")
      (node (ref "R16") (pin "1") (pinfunction "1_1") (pintype "passive"))
      (node (ref "U2") (pin "7") (pinfunction "Q7_7") (pintype "passive"))
    )
    (net (code "59") (name "Net-(U3-Q0)") (class "Default")
      (node (ref "R17") (pin "1") (pinfunction "1_1") (pintype "passive"))
      (node (ref "U3") (pin "15") (pinfunction "Q0_15") (pintype "passive"))
    )
    (net (code "60") (name "Net-(U3-Q1)") (class "Default")
      (node (ref "R18") (pin "1") (pinfunction "1_1") (pintype "passive"))
      (node (ref "U3") (pin "1") (pinfunction "Q1_1") (pintype "passive"))
    )
    (net (code "61") (name "Net-(U3-Q2)") (class "Default")
      (node (ref "R19") (pin "1") (pinfunction "1_1") (pintype "passive"))
      (node (ref "U3") (pin "2") (pinfunction "Q2_2") (pintype "passive"))
    )
    (net (code "62") (name "Net-(U3-Q3)") (class "Default")
      (node (ref "R20") (pin "1") (pinfunction "1_1") (pintype "passive"))
      (node (ref "U3") (pin "3") (pinfunction "Q3_3") (pintype "passive"))
    )
    (net (code "63") (name "Net-(U3-Q4)") (class "Default")
      (node (ref "R21") (pin "1") (pinfunction "1_1") (pintype "passive"))
      (node (ref "U3") (pin "4") (pinfunction "Q4_4") (pintype "passive"))
    )
    (net (code "64") (name "Net-(U3-Q5)") (class "Default")
      (node (ref "R22") (pin "1") (pinfunction "1_1") (pintype "passive"))
      (node (ref "U3") (pin "5") (pinfunction "Q5_5") (pintype "passive"))
    )
    (net (code "65") (name "Net-(U3-Q6)") (class "Default")
      (node (ref "R23") (pin "1") (pinfunction "1_1") (pintype "passive"))
      (node (ref "U3") (pin "6") (pinfunction "Q6_6") (pintype "passive"))
    )
    (net (code "66") (name "Net-(U3-Q7')") (class "Default")
      (node (ref "U3") (pin "9") (pinfunction "Q7'_9") (pintype "passive"))
      (node (ref "U4") (pin "14") (pinfunction "DS_14") (pintype "passive"))
    )
    (net (code "67") (name "Net-(U3-Q7)") (class "Default")
      (node (ref "R24") (pin "1") (pinfunction "1_1") (pintype "passive"))
      (node (ref "U3") (pin "7") (pinfunction "Q7_7") (pintype "passive"))
    )
    (net (code "68") (name "Net-(U4-Q0)") (class "Default")
      (node (ref "R25") (pin "1") (pinfunction "1_1") (pintype "passive"))
      (node (ref "U4") (pin "15") (pinfunction "Q0_15") (pintype "passive"))
    )
    (net (code "69") (name "Net-(U4-Q1)") (class "Default")
      (node (ref "R26") (pin "1") (pinfunction "1_1") (pintype "passive"))
      (node (ref "U4") (pin "1") (pinfunction "Q1_1") (pintype "passive"))
    )
    (net (code "70") (name "Net-(U4-Q2)") (class "Default")
      (node (ref "R27") (pin "1") (pinfunction "1_1") (pintype "passive"))
      (node (ref "U4") (pin "2") (pinfunction "Q2_2") (pintype "passive"))
    )
    (net (code "71") (name "Net-(U4-Q3)") (class "Default")
      (node (ref "R28") (pin "1") (pinfunction "1_1") (pintype "passive"))
      (node (ref "U4") (pin "3") (pinfunction "Q3_3") (pintype "passive"))
    )
    (net (code "72") (name "Net-(U4-Q4)") (class "Default")
      (node (ref "R29") (pin "1") (pinfunction "1_1") (pintype "passive"))
      (node (ref "U4") (pin "4") (pinfunction "Q4_4") (pintype "passive"))
    )
    (net (code "73") (name "Net-(U4-Q5)") (class "Default")
      (node (ref "R30") (pin "1") (pinfunction "1_1") (pintype "passive"))
      (node (ref "U4") (pin "5") (pinfunction "Q5_5") (pintype "passive"))
    )
    (net (code "74") (name "Net-(U4-Q6)") (class "Default")
      (node (ref "R31") (pin "1") (pinfunction "1_1") (pintype "passive"))
      (node (ref "U4") (pin "6") (pinfunction "Q6_6") (pintype "passive"))
    )
    (net (code "75") (name "Net-(U4-Q7)") (class "Default")
      (node (ref "R32") (pin "1") (pinfunction "1_1") (pintype "passive"))
      (node (ref "U4") (pin "7") (pinfunction "Q7_7") (pintype "passive"))
    )
    (net (code "76") (name "Net-(U5-IN)") (class "Default")
      (node (ref "C5") (pin "2") (pinfunction "2_2") (pintype "passive"))
      (node (ref "J1") (pin "1") (pinfunction "1_1") (pintype "passive"))
      (node (ref "U5") (pin "1") (pinfunction "IN_1") (pintype "passive"))
    )
    (net (code "77") (name "unconnected-(J1-Pad3)") (class "Default")
      (node (ref "J1") (pin "3") (pinfunction "3_3") (pintype "passive"))
    )
    (net (code "78") (name "unconnected-(J2-Pad1)") (class "Default")
      (node (ref "J2") (pin "1") (pinfunction "1_1") (pintype "passive+no_connect"))
    )
    (net (code "79") (name "unconnected-(J2-Pad2)") (class "Default")
      (node (ref "J2") (pin "2") (pinfunction "2_2") (pintype "passive+no_connect"))
    )
    (net (code "80") (name "unconnected-(J2-Pad3)") (class "Default")
      (node (ref "J2") (pin "3") (pinfunction "3_3") (pintype "passive+no_connect"))
    )
    (net (code "81") (name "unconnected-(J2-Pad4)") (class "Default")
      (node (ref "J2") (pin "4") (pinfunction "4_4") (pintype "passive+no_connect"))
    )
    (net (code "82") (name "unconnected-(J2-Pad5)") (class "Default")
      (node (ref "J2") (pin "5") (pinfunction "5_5") (pintype "passive+no_connect"))
    )
    (net (code "83") (name "unconnected-(J2-Pad6)") (class "Default")
      (node (ref "J2") (pin "6") (pinfunction "6_6") (pintype "passive+no_connect"))
    )
    (net (code "84") (name "unconnected-(J2-Pad7)") (class "Default")
      (node (ref "J2") (pin "7") (pinfunction "7_7") (pintype "passive+no_connect"))
    )
    (net (code "85") (name "unconnected-(J2-Pad8)") (class "Default")
      (node (ref "J2") (pin "8") (pinfunction "8_8") (pintype "passive+no_connect"))
    )
    (net (code "86") (name "unconnected-(J2-Pad9)") (class "Default")
      (node (ref "J2") (pin "9") (pinfunction "9_9") (pintype "passive+no_connect"))
    )
    (net (code "87") (name "unconnected-(J2-Pad10)") (class "Default")
      (node (ref "J2") (pin "10") (pinfunction "10_10") (pintype "passive+no_connect"))
    )
    (net (code "88") (name "unconnected-(J2-Pad11)") (class "Default")
      (node (ref "J2") (pin "11") (pinfunction "11_11") (pintype "passive+no_connect"))
    )
    (net (code "89") (name "unconnected-(J2-Pad12)") (class "Default")
      (node (ref "J2") (pin "12") (pinfunction "12_12") (pintype "passive+no_connect"))
    )
    (net (code "90") (name "unconnected-(J2-Pad13)") (class "Default")
      (node (ref "J2") (pin "13") (pinfunction "13_13") (pintype "passive+no_connect"))
    )
    (net (code "91") (name "unconnected-(J2-Pad14)") (class "Default")
      (node (ref "J2") (pin "14") (pinfunction "14_14") (pintype "passive+no_connect"))
    )
    (net (code "92") (name "unconnected-(J2-Pad15)") (class "Default")
      (node (ref "J2") (pin "15") (pinfunction "15_15") (pintype "passive+no_connect"))
    )
    (net (code "93") (name "unconnected-(J2-Pad16)") (class "Default")
      (node (ref "J2") (pin "16") (pinfunction "16_16") (pintype "passive+no_connect"))
    )
    (net (code "94") (name "unconnected-(J2-Pad17)") (class "Default")
      (node (ref "J2") (pin "17") (pinfunction "17_17") (pintype "passive+no_connect"))
    )
    (net (code "95") (name "unconnected-(J2-Pad18)") (class "Default")
      (node (ref "J2") (pin "18") (pinfunction "18_18") (pintype "passive+no_connect"))
    )
    (net (code "96") (name "unconnected-(J2-Pad19)") (class "Default")
      (node (ref "J2") (pin "19") (pinfunction "19_19") (pintype "passive+no_connect"))
    )
    (net (code "97") (name "unconnected-(J2-Pad20)") (class "Default")
      (node (ref "J2") (pin "20") (pinfunction "20_20") (pintype "passive+no_connect"))
    )
    (net (code "98") (name "unconnected-(J2-Pad21)") (class "Default")
      (node (ref "J2") (pin "21") (pinfunction "21_21") (pintype "passive+no_connect"))
    )
    (net (code "99") (name "unconnected-(J2-Pad22)") (class "Default")
      (node (ref "J2") (pin "22") (pinfunction "22_22") (pintype "passive+no_connect"))
    )
    (net (code "100") (name "unconnected-(J2-Pad23)") (class "Default")
      (node (ref "J2") (pin "23") (pinfunction "23_23") (pintype "passive+no_connect"))
    )
    (net (code "101") (name "unconnected-(J2-Pad24)") (class "Default")
      (node (ref "J2") (pin "24") (pinfunction "24_24") (pintype "passive+no_connect"))
    )
    (net (code "102") (name "unconnected-(J2-Pad25)") (class "Default")
      (node (ref "J2") (pin "25") (pinfunction "25_25") (pintype "passive+no_connect"))
    )
    (net (code "103") (name "unconnected-(J2-Pad26)") (class "Default")
      (node (ref "J2") (pin "26") (pinfunction "26_26") (pintype "passive+no_connect"))
    )
    (net (code "104") (name "unconnected-(J2-Pad27)") (class "Default")
      (node (ref "J2") (pin "27") (pinfunction "27_27") (pintype "passive+no_connect"))
    )
    (net (code "105") (name "unconnected-(J2-Pad28)") (class "Default")
      (node (ref "J2") (pin "28") (pinfunction "28_28") (pintype "passive+no_connect"))
    )
    (net (code "106") (name "unconnected-(J2-Pad29)") (class "Default")
      (node (ref "J2") (pin "29") (pinfunction "29_29") (pintype "passive+no_connect"))
    )
    (net (code "107") (name "unconnected-(J2-Pad30)") (class "Default")
      (node (ref "J2") (pin "30") (pinfunction "30_30") (pintype "passive+no_connect"))
    )
    (net (code "108") (name "unconnected-(J2-Pad31)") (class "Default")
      (node (ref "J2") (pin "31") (pinfunction "31_31") (pintype "passive+no_connect"))
    )
    (net (code "109") (name "unconnected-(J2-Pad32)") (class "Default")
      (node (ref "J2") (pin "32") (pinfunction "32_32") (pintype "passive+no_connect"))
    )
    (net (code "110") (name "unconnected-(J3-3.3V-Pad27)") (class "Default")
      (node (ref "J3") (pin "27") (pinfunction "3.3V_27") (pintype "passive+no_connect"))
    )
    (net (code "111") (name "unconnected-(J3-5V-Pad26)") (class "Default")
      (node (ref "J3") (pin "26") (pinfunction "5V_26") (pintype "passive+no_connect"))
    )
    (net (code "112") (name "unconnected-(J3-A0-Pad22)") (class "Default")
      (node (ref "J3") (pin "22") (pinfunction "A0_22") (pintype "passive+no_connect"))
    )
    (net (code "113") (name "unconnected-(J3-A1-Pad21)") (class "Default")
      (node (ref "J3") (pin "21") (pinfunction "A1_21") (pintype "passive+no_connect"))
    )
    (net (code "114") (name "unconnected-(J3-A2-Pad20)") (class "Default")
      (node (ref "J3") (pin "20") (pinfunction "A2_20") (pintype "passive+no_connect"))
    )
    (net (code "115") (name "unconnected-(J3-A3-Pad19)") (class "Default")
      (node (ref "J3") (pin "19") (pinfunction "A3_19") (pintype "passive+no_connect"))
    )
    (net (code "116") (name "unconnected-(J3-A4-Pad18)") (class "Default")
      (node (ref "J3") (pin "18") (pinfunction "A4_18") (pintype "passive+no_connect"))
    )
    (net (code "117") (name "unconnected-(J3-A5-Pad17)") (class "Default")
      (node (ref "J3") (pin "17") (pinfunction "A5_17") (pintype "passive+no_connect"))
    )
    (net (code "118") (name "unconnected-(J3-AREF-Pad16)") (class "Default")
      (node (ref "J3") (pin "16") (pinfunction "AREF_16") (pintype "passive+no_connect"))
    )
    (net (code "119") (name "unconnected-(J3-D0-Pad1)") (class "Default")
      (node (ref "J3") (pin "1") (pinfunction "D0_1") (pintype "passive+no_connect"))
    )
    (net (code "120") (name "unconnected-(J3-D1-Pad2)") (class "Default")
      (node (ref "J3") (pin "2") (pinfunction "D1_2") (pintype "passive+no_connect"))
    )
    (net (code "121") (name "unconnected-(J3-D2-Pad3)") (class "Default")
      (node (ref "J3") (pin "3") (pinfunction "D2_3") (pintype "passive+no_connect"))
    )
    (net (code "122") (name "unconnected-(J3-D3-Pad4)") (class "Default")
      (node (ref "J3") (pin "4") (pinfunction "D3_4") (pintype "passive+no_connect"))
    )
    (net (code "123") (name "unconnected-(J3-D4-Pad5)") (class "Default")
      (node (ref "J3") (pin "5") (pinfunction "D4_5") (pintype "passive+no_connect"))
    )
    (net (code "124") (name "unconnected-(J3-D8-Pad9)") (class "Default")
      (node (ref "J3") (pin "9") (pinfunction "D8_9") (pintype "passive+no_connect"))
    )
    (net (code "125") (name "unconnected-(J3-D9-Pad10)") (class "Default")
      (node (ref "J3") (pin "10") (pinfunction "D9_10") (pintype "passive+no_connect"))
    )
    (net (code "126") (name "unconnected-(J3-D11-Pad12)") (class "Default")
      (node (ref "J3") (pin "12") (pinfunction "D11_12") (pintype "passive+no_connect"))
    )
    (net (code "127") (name "unconnected-(J3-D12-Pad13)") (class "Default")
      (node (ref "J3") (pin "13") (pinfunction "D12_13") (pintype "passive+no_connect"))
    )
    (net (code "128") (name "unconnected-(J3-D13-Pad14)") (class "Default")
      (node (ref "J3") (pin "14") (pinfunction "D13_14") (pintype "passive+no_connect"))
    )
    (net (code "129") (name "unconnected-(J3-IOREF-Pad29)") (class "Default")
      (node (ref "J3") (pin "29") (pinfunction "IOREF_29") (pintype "passive+no_connect"))
    )
    (net (code "130") (name "unconnected-(J3-RESET-Pad28)") (class "Default")
      (node (ref "J3") (pin "28") (pinfunction "RESET_28") (pintype "passive+no_connect"))
    )
    (net (code "131") (name "unconnected-(J3-VIN-Pad23)") (class "Default")
      (node (ref "J3") (pin "23") (pinfunction "VIN_23") (pintype "passive+no_connect"))
    )
    (net (code "132") (name "unconnected-(U4-Q7'-Pad9)") (class "Default")
      (node (ref "U4") (pin "9") (pinfunction "Q7'_9") (pintype "passive+no_connect"))
    )
  )
)
